# qo-100-pa.net
KiCad netlist of a schematic drawn in EAGLE
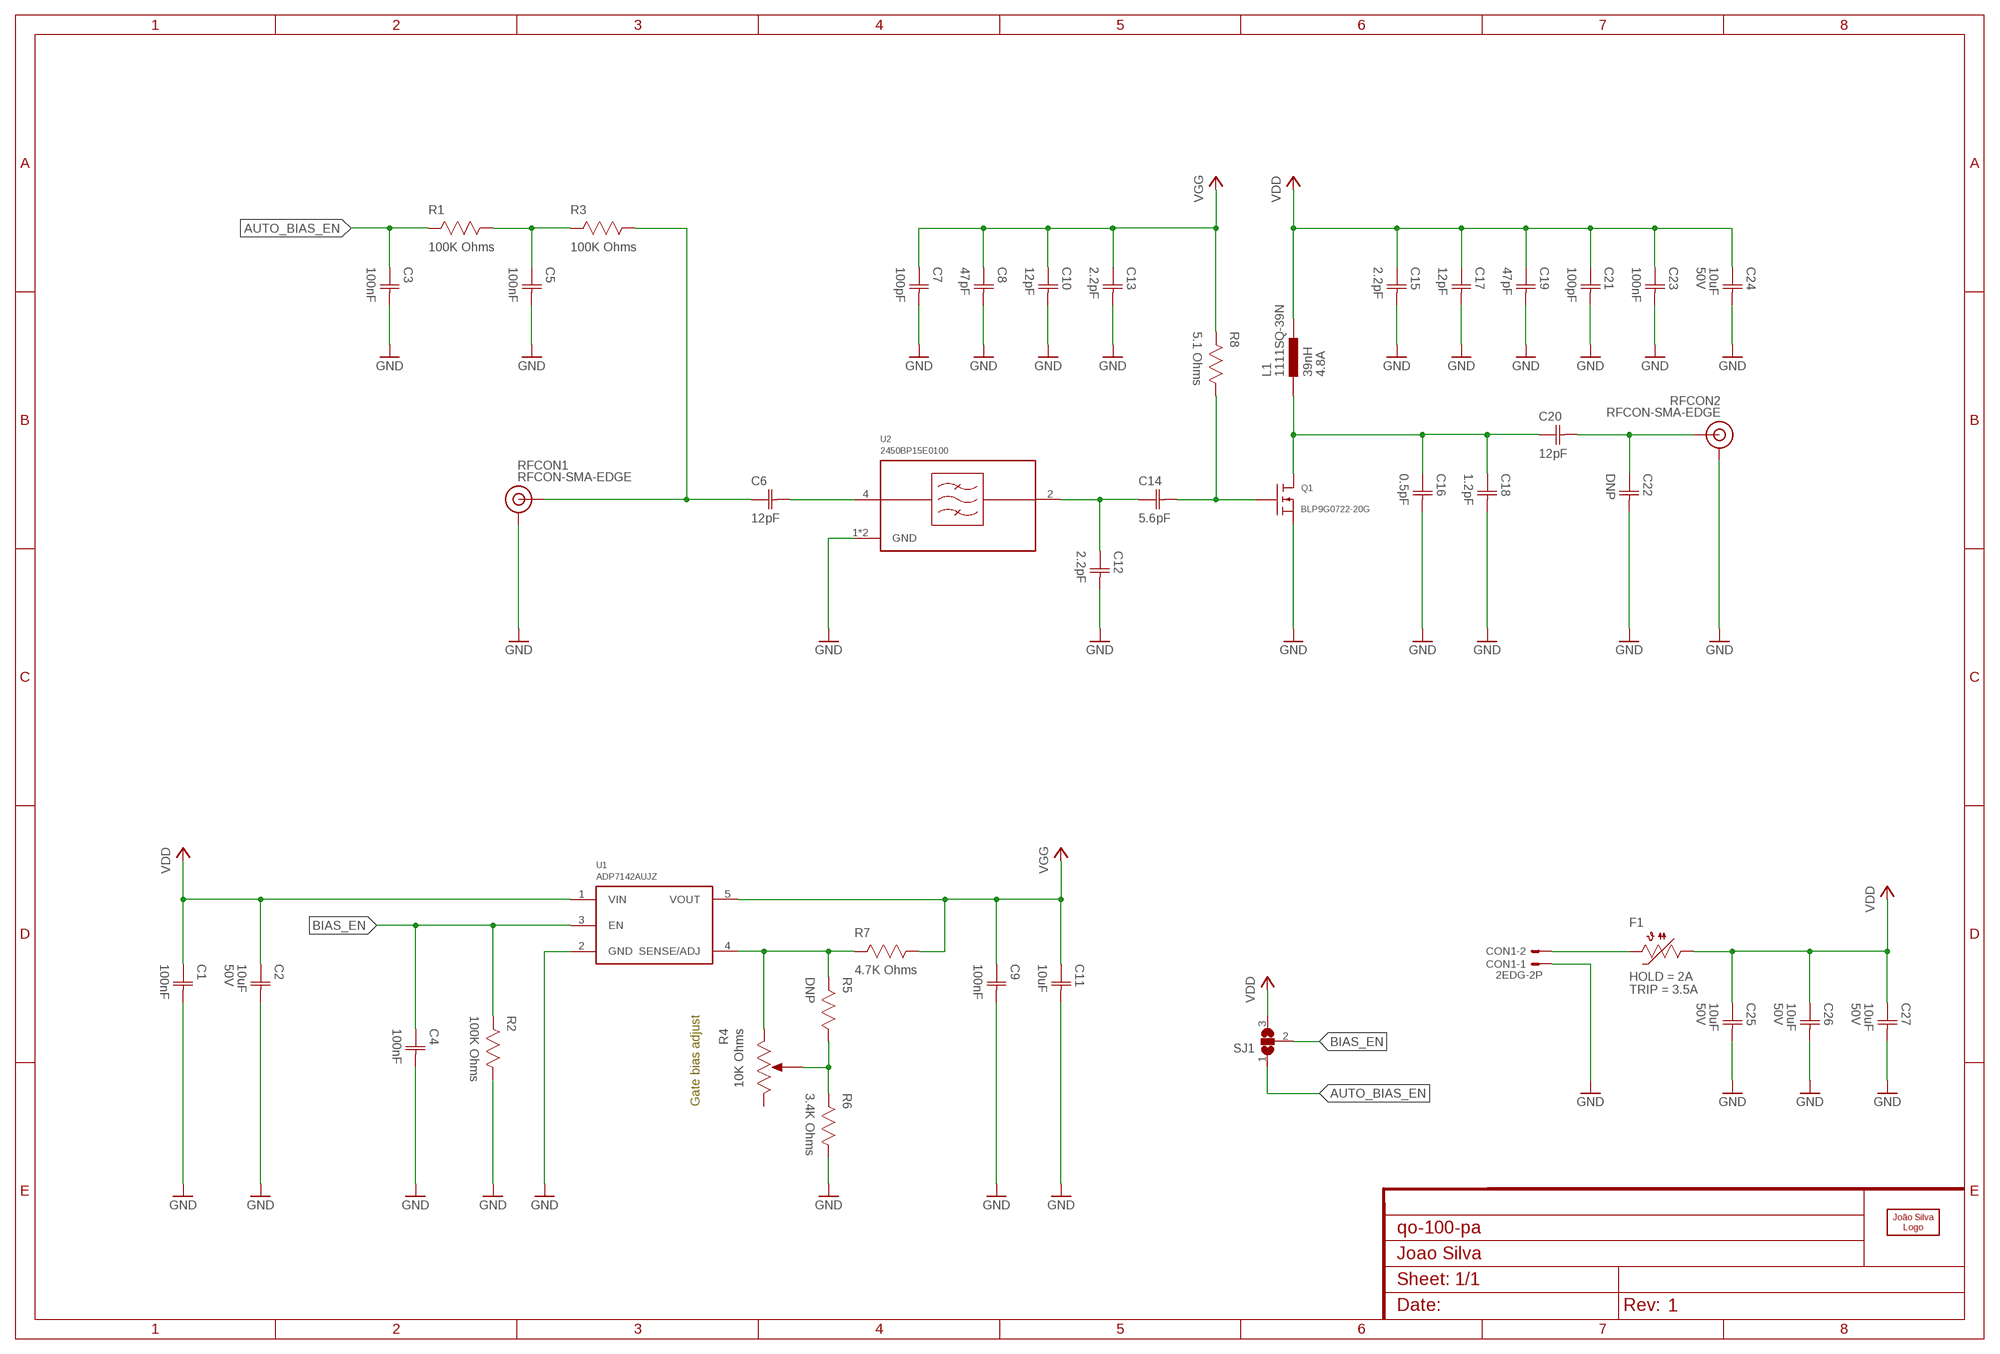
[diagram p0: schematic, sheet 1]

(export (version "E")
  (design (tool "Eeschema 10.0.6"))
  (components
    (comp (ref "C1")
      (value "100nF")
      (footprint "eagle-import:CAP0603")
      (libsource (lib "eagle-import") (part "CAPACITOR-0603"))
    )
    (comp (ref "C2")
      (value "10uF")
      (footprint "eagle-import:CAP1206")
      (fields (field (name "VOLTAGE") "50V"))
      (libsource (lib "eagle-import") (part "CAPACITOR-1206"))
    )
    (comp (ref "C3")
      (value "100nF")
      (footprint "eagle-import:CAP0603")
      (libsource (lib "eagle-import") (part "CAPACITOR-0603"))
    )
    (comp (ref "C4")
      (value "100nF")
      (footprint "eagle-import:CAP0603")
      (libsource (lib "eagle-import") (part "CAPACITOR-0603"))
    )
    (comp (ref "C5")
      (value "100nF")
      (footprint "eagle-import:CAP0603")
      (libsource (lib "eagle-import") (part "CAPACITOR-0603"))
    )
    (comp (ref "C6")
      (value "12pF")
      (footprint "eagle-import:CAP0603")
      (libsource (lib "eagle-import") (part "CAPACITOR-0603"))
    )
    (comp (ref "C7")
      (value "100pF")
      (footprint "eagle-import:CAP0603")
      (libsource (lib "eagle-import") (part "CAPACITOR-0603"))
    )
    (comp (ref "C8")
      (value "47pF")
      (footprint "eagle-import:CAP0603")
      (libsource (lib "eagle-import") (part "CAPACITOR-0603"))
    )
    (comp (ref "C9")
      (value "100nF")
      (footprint "eagle-import:CAP0603")
      (libsource (lib "eagle-import") (part "CAPACITOR-0603"))
    )
    (comp (ref "C10")
      (value "12pF")
      (footprint "eagle-import:CAP0603")
      (libsource (lib "eagle-import") (part "CAPACITOR-0603"))
    )
    (comp (ref "C11")
      (value "10uF")
      (footprint "eagle-import:CAP0603")
      (libsource (lib "eagle-import") (part "CAPACITOR-0603"))
    )
    (comp (ref "C12")
      (value "2.2pF")
      (footprint "eagle-import:CAP0603")
      (libsource (lib "eagle-import") (part "CAPACITOR-0603"))
    )
    (comp (ref "C13")
      (value "2.2pF")
      (footprint "eagle-import:CAP0603")
      (libsource (lib "eagle-import") (part "CAPACITOR-0603"))
    )
    (comp (ref "C14")
      (value "5.6pF")
      (footprint "eagle-import:CAP0603")
      (libsource (lib "eagle-import") (part "CAPACITOR-0603"))
    )
    (comp (ref "C15")
      (value "2.2pF")
      (footprint "eagle-import:CAP0603")
      (libsource (lib "eagle-import") (part "CAPACITOR-0603"))
    )
    (comp (ref "C16")
      (value "0.5pF")
      (footprint "eagle-import:CAP0603")
      (libsource (lib "eagle-import") (part "CAPACITOR-0603"))
    )
    (comp (ref "C17")
      (value "12pF")
      (footprint "eagle-import:CAP0603")
      (libsource (lib "eagle-import") (part "CAPACITOR-0603"))
    )
    (comp (ref "C18")
      (value "1.2pF")
      (footprint "eagle-import:CAP0603")
      (libsource (lib "eagle-import") (part "CAPACITOR-0603"))
    )
    (comp (ref "C19")
      (value "47pF")
      (footprint "eagle-import:CAP0603")
      (libsource (lib "eagle-import") (part "CAPACITOR-0603"))
    )
    (comp (ref "C20")
      (value "12pF")
      (footprint "eagle-import:CAP0603")
      (libsource (lib "eagle-import") (part "CAPACITOR-0603"))
    )
    (comp (ref "C21")
      (value "100pF")
      (footprint "eagle-import:CAP0603")
      (libsource (lib "eagle-import") (part "CAPACITOR-0603"))
    )
    (comp (ref "C22")
      (value "DNP")
      (footprint "eagle-import:CAP0603")
      (libsource (lib "eagle-import") (part "CAPACITOR-0603"))
    )
    (comp (ref "C23")
      (value "100nF")
      (footprint "eagle-import:CAP0603")
      (libsource (lib "eagle-import") (part "CAPACITOR-0603"))
    )
    (comp (ref "C24")
      (value "10uF")
      (footprint "eagle-import:CAP1206")
      (fields (field (name "VOLTAGE") "50V"))
      (libsource (lib "eagle-import") (part "CAPACITOR-1206"))
    )
    (comp (ref "C25")
      (value "10uF")
      (footprint "eagle-import:CAP1206")
      (fields (field (name "VOLTAGE") "50V"))
      (libsource (lib "eagle-import") (part "CAPACITOR-1206"))
    )
    (comp (ref "C26")
      (value "10uF")
      (footprint "eagle-import:CAP1206")
      (fields (field (name "VOLTAGE") "50V"))
      (libsource (lib "eagle-import") (part "CAPACITOR-1206"))
    )
    (comp (ref "C27")
      (value "10uF")
      (footprint "eagle-import:CAP1206")
      (fields (field (name "VOLTAGE") "50V"))
      (libsource (lib "eagle-import") (part "CAPACITOR-1206"))
    )
    (comp (ref "CON1")
      (value "2EDG-2P")
      (footprint "eagle-import:2EDG-2P")
      (libsource (lib "eagle-import") (part "2EDG-2P"))
    )
    (comp (ref "F1")
      (value "PTC1206")
      (footprint "eagle-import:1206")
      (fields (field (name "HOLD") "2A") (field (name "TRIP") "3.5A"))
      (libsource (lib "eagle-import") (part "PTC1206"))
    )
    (comp (ref "L1")
      (value "39nH")
      (footprint "eagle-import:1111SQ")
      (fields (field (name "CURRENT") "4.8A") (field (name "REF") "1111SQ-39N"))
      (libsource (lib "eagle-import") (part "1111SQ-39N"))
    )
    (comp (ref "LOGO1")
      (value "JS-10MM")
      (footprint "eagle-import:JS_10MM")
      (libsource (lib "eagle-import") (part "JS-10MM"))
    )
    (comp (ref "Q1")
      (value "BLP9G0722-20G")
      (footprint "eagle-import:SOT1483-1")
      (libsource (lib "eagle-import") (part "BLP9G0722-20G"))
    )
    (comp (ref "R1")
      (value "100K Ohms")
      (footprint "eagle-import:RES0603")
      (libsource (lib "eagle-import") (part "RESISTOR-0603"))
    )
    (comp (ref "R2")
      (value "100K Ohms")
      (footprint "eagle-import:RES0603")
      (libsource (lib "eagle-import") (part "RESISTOR-0603"))
    )
    (comp (ref "R3")
      (value "100K Ohms")
      (footprint "eagle-import:RES0603")
      (libsource (lib "eagle-import") (part "RESISTOR-0603"))
    )
    (comp (ref "R4")
      (value "10K Ohms")
      (footprint "eagle-import:POT3MM")
      (libsource (lib "eagle-import") (part "POTENTIOMETER-SMD-3X3"))
    )
    (comp (ref "R5")
      (value "DNP")
      (footprint "eagle-import:RES0603")
      (libsource (lib "eagle-import") (part "RESISTOR-0603"))
    )
    (comp (ref "R6")
      (value "3.4K Ohms")
      (footprint "eagle-import:RES0603")
      (libsource (lib "eagle-import") (part "RESISTOR-0603"))
    )
    (comp (ref "R7")
      (value "4.7K Ohms")
      (footprint "eagle-import:RES0603")
      (libsource (lib "eagle-import") (part "RESISTOR-0603"))
    )
    (comp (ref "R8")
      (value "5.1 Ohms")
      (footprint "eagle-import:RES0603")
      (libsource (lib "eagle-import") (part "RESISTOR-0603"))
    )
    (comp (ref "RFCON1")
      (value "RFCON-SMA-EDGE")
      (footprint "eagle-import:SMA-EDGE")
      (libsource (lib "eagle-import") (part "RFCON-SMA-EDGE"))
    )
    (comp (ref "RFCON2")
      (value "RFCON-SMA-EDGE")
      (footprint "eagle-import:SMA-EDGE")
      (libsource (lib "eagle-import") (part "RFCON-SMA-EDGE"))
    )
    (comp (ref "SJ1")
      (value "SJ2S")
      (footprint "eagle-import:SJ2_S")
      (libsource (lib "eagle-import") (part "SJ2S"))
    )
    (comp (ref "U1")
      (value "ADP7142AUJZ")
      (footprint "eagle-import:SOT23-5")
      (libsource (lib "eagle-import") (part "ADP7142AUJZ"))
    )
    (comp (ref "U2")
      (value "2450BP15E0100")
      (footprint "eagle-import:2450BP15E0100")
      (libsource (lib "eagle-import") (part "2450BP15E0100"))
    )
  )
  (nets
    (net (code "1") (name "AUTO_BIAS_EN") (class "Default")
      (node (ref "C3") (pin "1") (pinfunction "C1_1") (pintype "passive"))
      (node (ref "R1") (pin "2") (pinfunction "2_2") (pintype "passive"))
      (node (ref "SJ1") (pin "1") (pinfunction "1_1") (pintype "passive"))
    )
    (net (code "2") (name "BIAS_EN") (class "Default")
      (node (ref "C4") (pin "1") (pinfunction "C1_1") (pintype "passive"))
      (node (ref "R2") (pin "2") (pinfunction "2_2") (pintype "passive"))
      (node (ref "SJ1") (pin "2") (pinfunction "2_2") (pintype "passive"))
      (node (ref "U1") (pin "3") (pinfunction "EN_3") (pintype "bidirectional"))
    )
    (net (code "3") (name "GND") (class "Default")
      (node (ref "C1") (pin "2") (pinfunction "C2_2") (pintype "passive"))
      (node (ref "C10") (pin "2") (pinfunction "C2_2") (pintype "passive"))
      (node (ref "C11") (pin "2") (pinfunction "C2_2") (pintype "passive"))
      (node (ref "C12") (pin "2") (pinfunction "C2_2") (pintype "passive"))
      (node (ref "C13") (pin "2") (pinfunction "C2_2") (pintype "passive"))
      (node (ref "C15") (pin "2") (pinfunction "C2_2") (pintype "passive"))
      (node (ref "C16") (pin "2") (pinfunction "C2_2") (pintype "passive"))
      (node (ref "C17") (pin "2") (pinfunction "C2_2") (pintype "passive"))
      (node (ref "C18") (pin "2") (pinfunction "C2_2") (pintype "passive"))
      (node (ref "C19") (pin "2") (pinfunction "C2_2") (pintype "passive"))
      (node (ref "C2") (pin "2") (pinfunction "C2_2") (pintype "passive"))
      (node (ref "C21") (pin "2") (pinfunction "C2_2") (pintype "passive"))
      (node (ref "C22") (pin "2") (pinfunction "C2_2") (pintype "passive"))
      (node (ref "C23") (pin "2") (pinfunction "C2_2") (pintype "passive"))
      (node (ref "C24") (pin "2") (pinfunction "C2_2") (pintype "passive"))
      (node (ref "C25") (pin "2") (pinfunction "C2_2") (pintype "passive"))
      (node (ref "C26") (pin "2") (pinfunction "C2_2") (pintype "passive"))
      (node (ref "C27") (pin "2") (pinfunction "C2_2") (pintype "passive"))
      (node (ref "C3") (pin "2") (pinfunction "C2_2") (pintype "passive"))
      (node (ref "C4") (pin "2") (pinfunction "C2_2") (pintype "passive"))
      (node (ref "C5") (pin "2") (pinfunction "C2_2") (pintype "passive"))
      (node (ref "C7") (pin "2") (pinfunction "C2_2") (pintype "passive"))
      (node (ref "C8") (pin "2") (pinfunction "C2_2") (pintype "passive"))
      (node (ref "C9") (pin "2") (pinfunction "C2_2") (pintype "passive"))
      (node (ref "CON1") (pin "P$1") (pinfunction "S_P$1") (pintype "passive"))
      (node (ref "Q1") (pin "3@0") (pinfunction "S_3@0") (pintype "passive"))
      (node (ref "Q1") (pin "3@1") (pinfunction "S_3@1") (pintype "passive"))
      (node (ref "Q1") (pin "3@2") (pinfunction "S_3@2") (pintype "passive"))
      (node (ref "R2") (pin "1") (pinfunction "1_1") (pintype "passive"))
      (node (ref "R6") (pin "1") (pinfunction "1_1") (pintype "passive"))
      (node (ref "RFCON1") (pin "GND@0") (pinfunction "GND_GND@0") (pintype "bidirectional"))
      (node (ref "RFCON1") (pin "GND@1") (pinfunction "GND_GND@1") (pintype "bidirectional"))
      (node (ref "RFCON1") (pin "GND@2") (pinfunction "GND_GND@2") (pintype "bidirectional"))
      (node (ref "RFCON1") (pin "GND@3") (pinfunction "GND_GND@3") (pintype "bidirectional"))
      (node (ref "RFCON2") (pin "GND@0") (pinfunction "GND_GND@0") (pintype "bidirectional"))
      (node (ref "RFCON2") (pin "GND@1") (pinfunction "GND_GND@1") (pintype "bidirectional"))
      (node (ref "RFCON2") (pin "GND@2") (pinfunction "GND_GND@2") (pintype "bidirectional"))
      (node (ref "RFCON2") (pin "GND@3") (pinfunction "GND_GND@3") (pintype "bidirectional"))
      (node (ref "U1") (pin "2") (pinfunction "GND_2") (pintype "bidirectional"))
      (node (ref "U2") (pin "1") (pinfunction "GND_1") (pintype "bidirectional"))
      (node (ref "U2") (pin "3") (pinfunction "GND_3") (pintype "bidirectional"))
    )
    (net (code "4") (name "Net-(C5-C1)") (class "Default")
      (node (ref "C5") (pin "1") (pinfunction "C1_1") (pintype "passive"))
      (node (ref "R1") (pin "1") (pinfunction "1_1") (pintype "passive"))
      (node (ref "R3") (pin "2") (pinfunction "2_2") (pintype "passive"))
    )
    (net (code "5") (name "Net-(C6-C1)") (class "Default")
      (node (ref "C6") (pin "1") (pinfunction "C1_1") (pintype "passive"))
      (node (ref "R3") (pin "1") (pinfunction "1_1") (pintype "passive"))
      (node (ref "RFCON1") (pin "SIG") (pinfunction "SIGNAL_SIG") (pintype "bidirectional"))
    )
    (net (code "6") (name "Net-(C6-C2)") (class "Default")
      (node (ref "C6") (pin "2") (pinfunction "C2_2") (pintype "passive"))
      (node (ref "U2") (pin "4") (pinfunction "RFIN_4") (pintype "bidirectional"))
    )
    (net (code "7") (name "Net-(C12-C1)") (class "Default")
      (node (ref "C12") (pin "1") (pinfunction "C1_1") (pintype "passive"))
      (node (ref "C14") (pin "1") (pinfunction "C1_1") (pintype "passive"))
      (node (ref "U2") (pin "2") (pinfunction "RFOUT_2") (pintype "bidirectional"))
    )
    (net (code "8") (name "Net-(C14-C2)") (class "Default")
      (node (ref "C14") (pin "2") (pinfunction "C2_2") (pintype "passive"))
      (node (ref "Q1") (pin "2") (pinfunction "G_2") (pintype "passive"))
      (node (ref "R8") (pin "1") (pinfunction "1_1") (pintype "passive"))
    )
    (net (code "9") (name "Net-(C16-C1)") (class "Default")
      (node (ref "C16") (pin "1") (pinfunction "C1_1") (pintype "passive"))
      (node (ref "C18") (pin "1") (pinfunction "C1_1") (pintype "passive"))
      (node (ref "C20") (pin "1") (pinfunction "C1_1") (pintype "passive"))
      (node (ref "L1") (pin "1") (pinfunction "1_1") (pintype "passive"))
      (node (ref "Q1") (pin "1") (pinfunction "D_1") (pintype "passive"))
    )
    (net (code "10") (name "Net-(C20-C2)") (class "Default")
      (node (ref "C20") (pin "2") (pinfunction "C2_2") (pintype "passive"))
      (node (ref "C22") (pin "1") (pinfunction "C1_1") (pintype "passive"))
      (node (ref "RFCON2") (pin "SIG") (pinfunction "SIGNAL_SIG") (pintype "bidirectional"))
    )
    (net (code "11") (name "Net-(CON1B-S)") (class "Default")
      (node (ref "CON1") (pin "P$2") (pinfunction "S_P$2") (pintype "passive"))
      (node (ref "F1") (pin "2") (pinfunction "2_2") (pintype "passive"))
    )
    (net (code "12") (name "Net-(R4-CCW)") (class "Default")
      (node (ref "R4") (pin "1") (pinfunction "CCW_1") (pintype "passive"))
      (node (ref "R5") (pin "2") (pinfunction "2_2") (pintype "passive"))
      (node (ref "R7") (pin "2") (pinfunction "2_2") (pintype "passive"))
      (node (ref "U1") (pin "4") (pinfunction "SENSE/ADJ_4") (pintype "bidirectional"))
    )
    (net (code "13") (name "Net-(R4-WIPER)") (class "Default")
      (node (ref "R4") (pin "2") (pinfunction "WIPER_2") (pintype "passive"))
      (node (ref "R5") (pin "1") (pinfunction "1_1") (pintype "passive"))
      (node (ref "R6") (pin "2") (pinfunction "2_2") (pintype "passive"))
    )
    (net (code "14") (name "VDD") (class "Default")
      (node (ref "C1") (pin "1") (pinfunction "C1_1") (pintype "passive"))
      (node (ref "C15") (pin "1") (pinfunction "C1_1") (pintype "passive"))
      (node (ref "C17") (pin "1") (pinfunction "C1_1") (pintype "passive"))
      (node (ref "C19") (pin "1") (pinfunction "C1_1") (pintype "passive"))
      (node (ref "C2") (pin "1") (pinfunction "C1_1") (pintype "passive"))
      (node (ref "C21") (pin "1") (pinfunction "C1_1") (pintype "passive"))
      (node (ref "C23") (pin "1") (pinfunction "C1_1") (pintype "passive"))
      (node (ref "C24") (pin "1") (pinfunction "C1_1") (pintype "passive"))
      (node (ref "C25") (pin "1") (pinfunction "C1_1") (pintype "passive"))
      (node (ref "C26") (pin "1") (pinfunction "C1_1") (pintype "passive"))
      (node (ref "C27") (pin "1") (pinfunction "C1_1") (pintype "passive"))
      (node (ref "F1") (pin "1") (pinfunction "1_1") (pintype "passive"))
      (node (ref "L1") (pin "2") (pinfunction "2_2") (pintype "passive"))
      (node (ref "SJ1") (pin "3") (pinfunction "3_3") (pintype "passive"))
      (node (ref "U1") (pin "1") (pinfunction "VIN_1") (pintype "bidirectional"))
    )
    (net (code "15") (name "VGG") (class "Default")
      (node (ref "C10") (pin "1") (pinfunction "C1_1") (pintype "passive"))
      (node (ref "C11") (pin "1") (pinfunction "C1_1") (pintype "passive"))
      (node (ref "C13") (pin "1") (pinfunction "C1_1") (pintype "passive"))
      (node (ref "C7") (pin "1") (pinfunction "C1_1") (pintype "passive"))
      (node (ref "C8") (pin "1") (pinfunction "C1_1") (pintype "passive"))
      (node (ref "C9") (pin "1") (pinfunction "C1_1") (pintype "passive"))
      (node (ref "R7") (pin "1") (pinfunction "1_1") (pintype "passive"))
      (node (ref "R8") (pin "2") (pinfunction "2_2") (pintype "passive"))
      (node (ref "U1") (pin "5") (pinfunction "VOUT_5") (pintype "bidirectional"))
    )
    (net (code "16") (name "unconnected-(R4-CW-Pad3)") (class "Default")
      (node (ref "R4") (pin "3") (pinfunction "CW_3") (pintype "passive"))
    )
  )
)
